# M903B.net
KiCad netlist of a schematic drawn in EAGLE
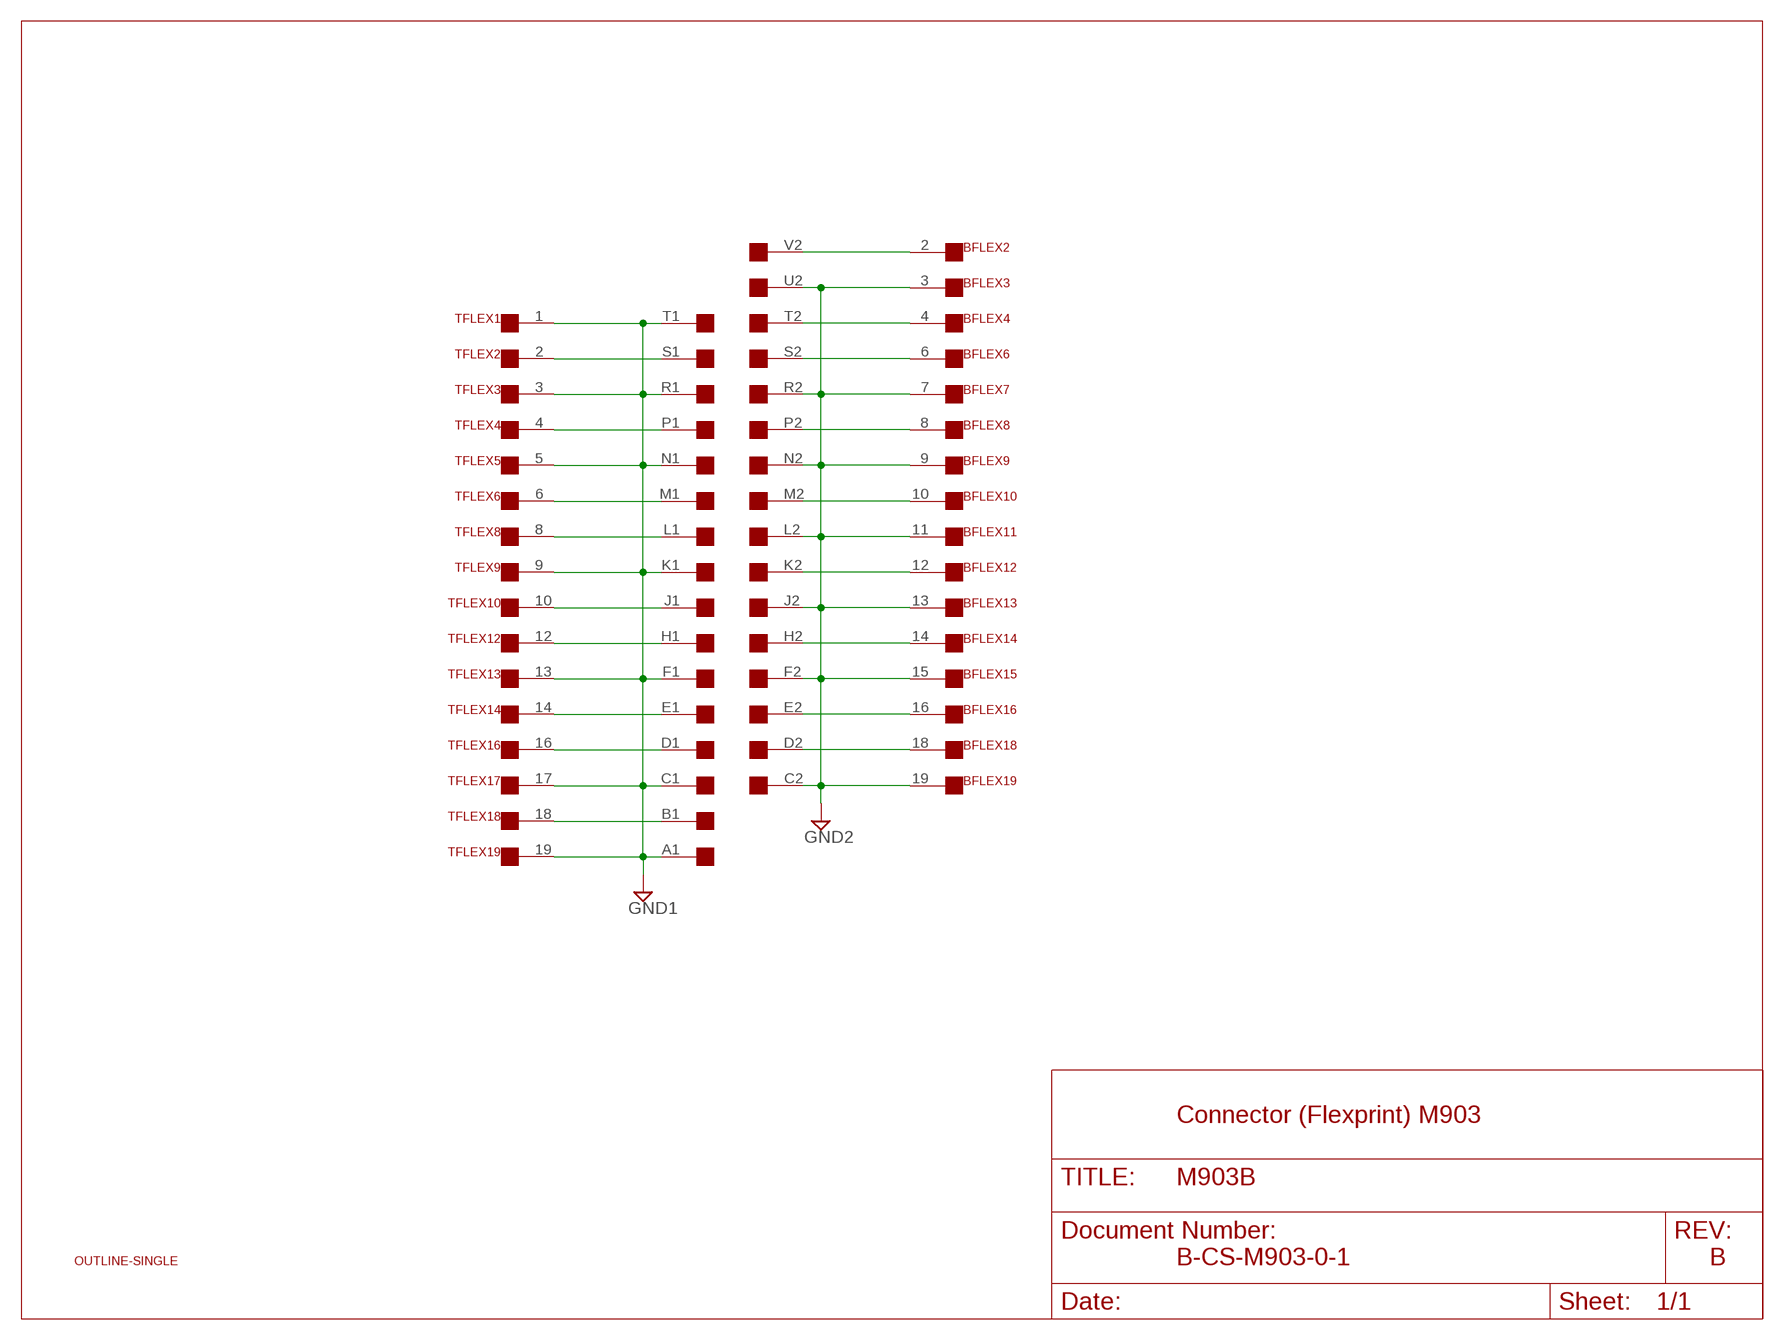
[diagram p0: schematic, sheet 1]

(export (version "E")
  (design (tool "Eeschema 10.0.6"))
  (components
    (comp (ref "BFLEX")
      (value "FLEX19")
      (footprint "eagle-import:FLEX19")
      (libsource (lib "eagle-import") (part "FLEX19"))
    )
    (comp (ref "TFLEX")
      (value "FLEX19")
      (footprint "eagle-import:FLEX19")
      (libsource (lib "eagle-import") (part "FLEX19"))
    )
    (comp (ref "U$1")
      (value "SINGLE")
      (footprint "eagle-import:EDGE-CON2")
      (libsource (lib "eagle-import") (part "SINGLE"))
    )
    (comp (ref "U$2")
      (value "OUTLINE-SINGLE")
      (footprint "eagle-import:SINGLE")
      (libsource (lib "eagle-import") (part "OUTLINE-SINGLE"))
    )
  )
  (nets
    (net (code "1") (name "GND1") (class "Default")
      (node (ref "TFLEX") (pin "1") (pinfunction "1_1") (pintype "passive"))
      (node (ref "TFLEX") (pin "13") (pinfunction "1_13") (pintype "passive"))
      (node (ref "TFLEX") (pin "17") (pinfunction "1_17") (pintype "passive"))
      (node (ref "TFLEX") (pin "19") (pinfunction "1_19") (pintype "passive"))
      (node (ref "TFLEX") (pin "3") (pinfunction "1_3") (pintype "passive"))
      (node (ref "TFLEX") (pin "5") (pinfunction "1_5") (pintype "passive"))
      (node (ref "TFLEX") (pin "9") (pinfunction "1_9") (pintype "passive"))
      (node (ref "U$1") (pin "A1") (pinfunction "1_A1") (pintype "bidirectional"))
      (node (ref "U$1") (pin "C1") (pinfunction "1_C1") (pintype "bidirectional"))
      (node (ref "U$1") (pin "F1") (pinfunction "1_F1") (pintype "bidirectional"))
      (node (ref "U$1") (pin "K1") (pinfunction "1_K1") (pintype "bidirectional"))
      (node (ref "U$1") (pin "N1") (pinfunction "1_N1") (pintype "bidirectional"))
      (node (ref "U$1") (pin "R1") (pinfunction "1_R1") (pintype "bidirectional"))
      (node (ref "U$1") (pin "T1") (pinfunction "1_T1") (pintype "bidirectional"))
    )
    (net (code "2") (name "GND2") (class "Default")
      (node (ref "BFLEX") (pin "11") (pinfunction "1_11") (pintype "passive"))
      (node (ref "BFLEX") (pin "13") (pinfunction "1_13") (pintype "passive"))
      (node (ref "BFLEX") (pin "15") (pinfunction "1_15") (pintype "passive"))
      (node (ref "BFLEX") (pin "19") (pinfunction "1_19") (pintype "passive"))
      (node (ref "BFLEX") (pin "3") (pinfunction "1_3") (pintype "passive"))
      (node (ref "BFLEX") (pin "7") (pinfunction "1_7") (pintype "passive"))
      (node (ref "BFLEX") (pin "9") (pinfunction "1_9") (pintype "passive"))
      (node (ref "U$1") (pin "C2") (pinfunction "1_C2") (pintype "bidirectional"))
      (node (ref "U$1") (pin "F2") (pinfunction "1_F2") (pintype "bidirectional"))
      (node (ref "U$1") (pin "J2") (pinfunction "1_J2") (pintype "bidirectional"))
      (node (ref "U$1") (pin "L2") (pinfunction "1_L2") (pintype "bidirectional"))
      (node (ref "U$1") (pin "N2") (pinfunction "1_N2") (pintype "bidirectional"))
      (node (ref "U$1") (pin "R2") (pinfunction "1_R2") (pintype "bidirectional"))
      (node (ref "U$1") (pin "U2") (pinfunction "1_U2") (pintype "bidirectional"))
    )
    (net (code "3") (name "Net-(BFLEXB-1)") (class "Default")
      (node (ref "BFLEX") (pin "10") (pinfunction "1_10") (pintype "passive"))
      (node (ref "U$1") (pin "M2") (pinfunction "1_M2") (pintype "bidirectional"))
    )
    (net (code "4") (name "Net-(BFLEXD-1)") (class "Default")
      (node (ref "BFLEX") (pin "12") (pinfunction "1_12") (pintype "passive"))
      (node (ref "U$1") (pin "K2") (pinfunction "1_K2") (pintype "bidirectional"))
    )
    (net (code "5") (name "Net-(BFLEXF-1)") (class "Default")
      (node (ref "BFLEX") (pin "14") (pinfunction "1_14") (pintype "passive"))
      (node (ref "U$1") (pin "H2") (pinfunction "1_H2") (pintype "bidirectional"))
    )
    (net (code "6") (name "Net-(BFLEXH-1)") (class "Default")
      (node (ref "BFLEX") (pin "16") (pinfunction "1_16") (pintype "passive"))
      (node (ref "U$1") (pin "E2") (pinfunction "1_E2") (pintype "bidirectional"))
    )
    (net (code "7") (name "Net-(BFLEXJ-1)") (class "Default")
      (node (ref "BFLEX") (pin "18") (pinfunction "1_18") (pintype "passive"))
      (node (ref "U$1") (pin "D2") (pinfunction "1_D2") (pintype "bidirectional"))
    )
    (net (code "8") (name "Net-(BFLEXL-1)") (class "Default")
      (node (ref "BFLEX") (pin "2") (pinfunction "1_2") (pintype "passive"))
      (node (ref "U$1") (pin "V2") (pinfunction "1_V2") (pintype "bidirectional"))
    )
    (net (code "9") (name "Net-(BFLEXN-1)") (class "Default")
      (node (ref "BFLEX") (pin "4") (pinfunction "1_4") (pintype "passive"))
      (node (ref "U$1") (pin "T2") (pinfunction "1_T2") (pintype "bidirectional"))
    )
    (net (code "10") (name "Net-(BFLEXP-1)") (class "Default")
      (node (ref "BFLEX") (pin "6") (pinfunction "1_6") (pintype "passive"))
      (node (ref "U$1") (pin "S2") (pinfunction "1_S2") (pintype "bidirectional"))
    )
    (net (code "11") (name "Net-(BFLEXR-1)") (class "Default")
      (node (ref "BFLEX") (pin "8") (pinfunction "1_8") (pintype "passive"))
      (node (ref "U$1") (pin "P2") (pinfunction "1_P2") (pintype "bidirectional"))
    )
    (net (code "12") (name "Net-(TFLEXB-1)") (class "Default")
      (node (ref "TFLEX") (pin "10") (pinfunction "1_10") (pintype "passive"))
      (node (ref "U$1") (pin "J1") (pinfunction "1_J1") (pintype "bidirectional"))
    )
    (net (code "13") (name "Net-(TFLEXD-1)") (class "Default")
      (node (ref "TFLEX") (pin "12") (pinfunction "1_12") (pintype "passive"))
      (node (ref "U$1") (pin "H1") (pinfunction "1_H1") (pintype "bidirectional"))
    )
    (net (code "14") (name "Net-(TFLEXF-1)") (class "Default")
      (node (ref "TFLEX") (pin "14") (pinfunction "1_14") (pintype "passive"))
      (node (ref "U$1") (pin "E1") (pinfunction "1_E1") (pintype "bidirectional"))
    )
    (net (code "15") (name "Net-(TFLEXH-1)") (class "Default")
      (node (ref "TFLEX") (pin "16") (pinfunction "1_16") (pintype "passive"))
      (node (ref "U$1") (pin "D1") (pinfunction "1_D1") (pintype "bidirectional"))
    )
    (net (code "16") (name "Net-(TFLEXJ-1)") (class "Default")
      (node (ref "TFLEX") (pin "18") (pinfunction "1_18") (pintype "passive"))
      (node (ref "U$1") (pin "B1") (pinfunction "1_B1") (pintype "bidirectional"))
    )
    (net (code "17") (name "Net-(TFLEXL-1)") (class "Default")
      (node (ref "TFLEX") (pin "2") (pinfunction "1_2") (pintype "passive"))
      (node (ref "U$1") (pin "S1") (pinfunction "1_S1") (pintype "bidirectional"))
    )
    (net (code "18") (name "Net-(TFLEXN-1)") (class "Default")
      (node (ref "TFLEX") (pin "4") (pinfunction "1_4") (pintype "passive"))
      (node (ref "U$1") (pin "P1") (pinfunction "1_P1") (pintype "bidirectional"))
    )
    (net (code "19") (name "Net-(TFLEXP-1)") (class "Default")
      (node (ref "TFLEX") (pin "6") (pinfunction "1_6") (pintype "passive"))
      (node (ref "U$1") (pin "M1") (pinfunction "1_M1") (pintype "bidirectional"))
    )
    (net (code "20") (name "Net-(TFLEXR-1)") (class "Default")
      (node (ref "TFLEX") (pin "8") (pinfunction "1_8") (pintype "passive"))
      (node (ref "U$1") (pin "L1") (pinfunction "1_L1") (pintype "bidirectional"))
    )
  )
)
